# Callisto_Teknic_MSO_PBx4_v1p2.net
KiCad netlist of a schematic drawn in EAGLE
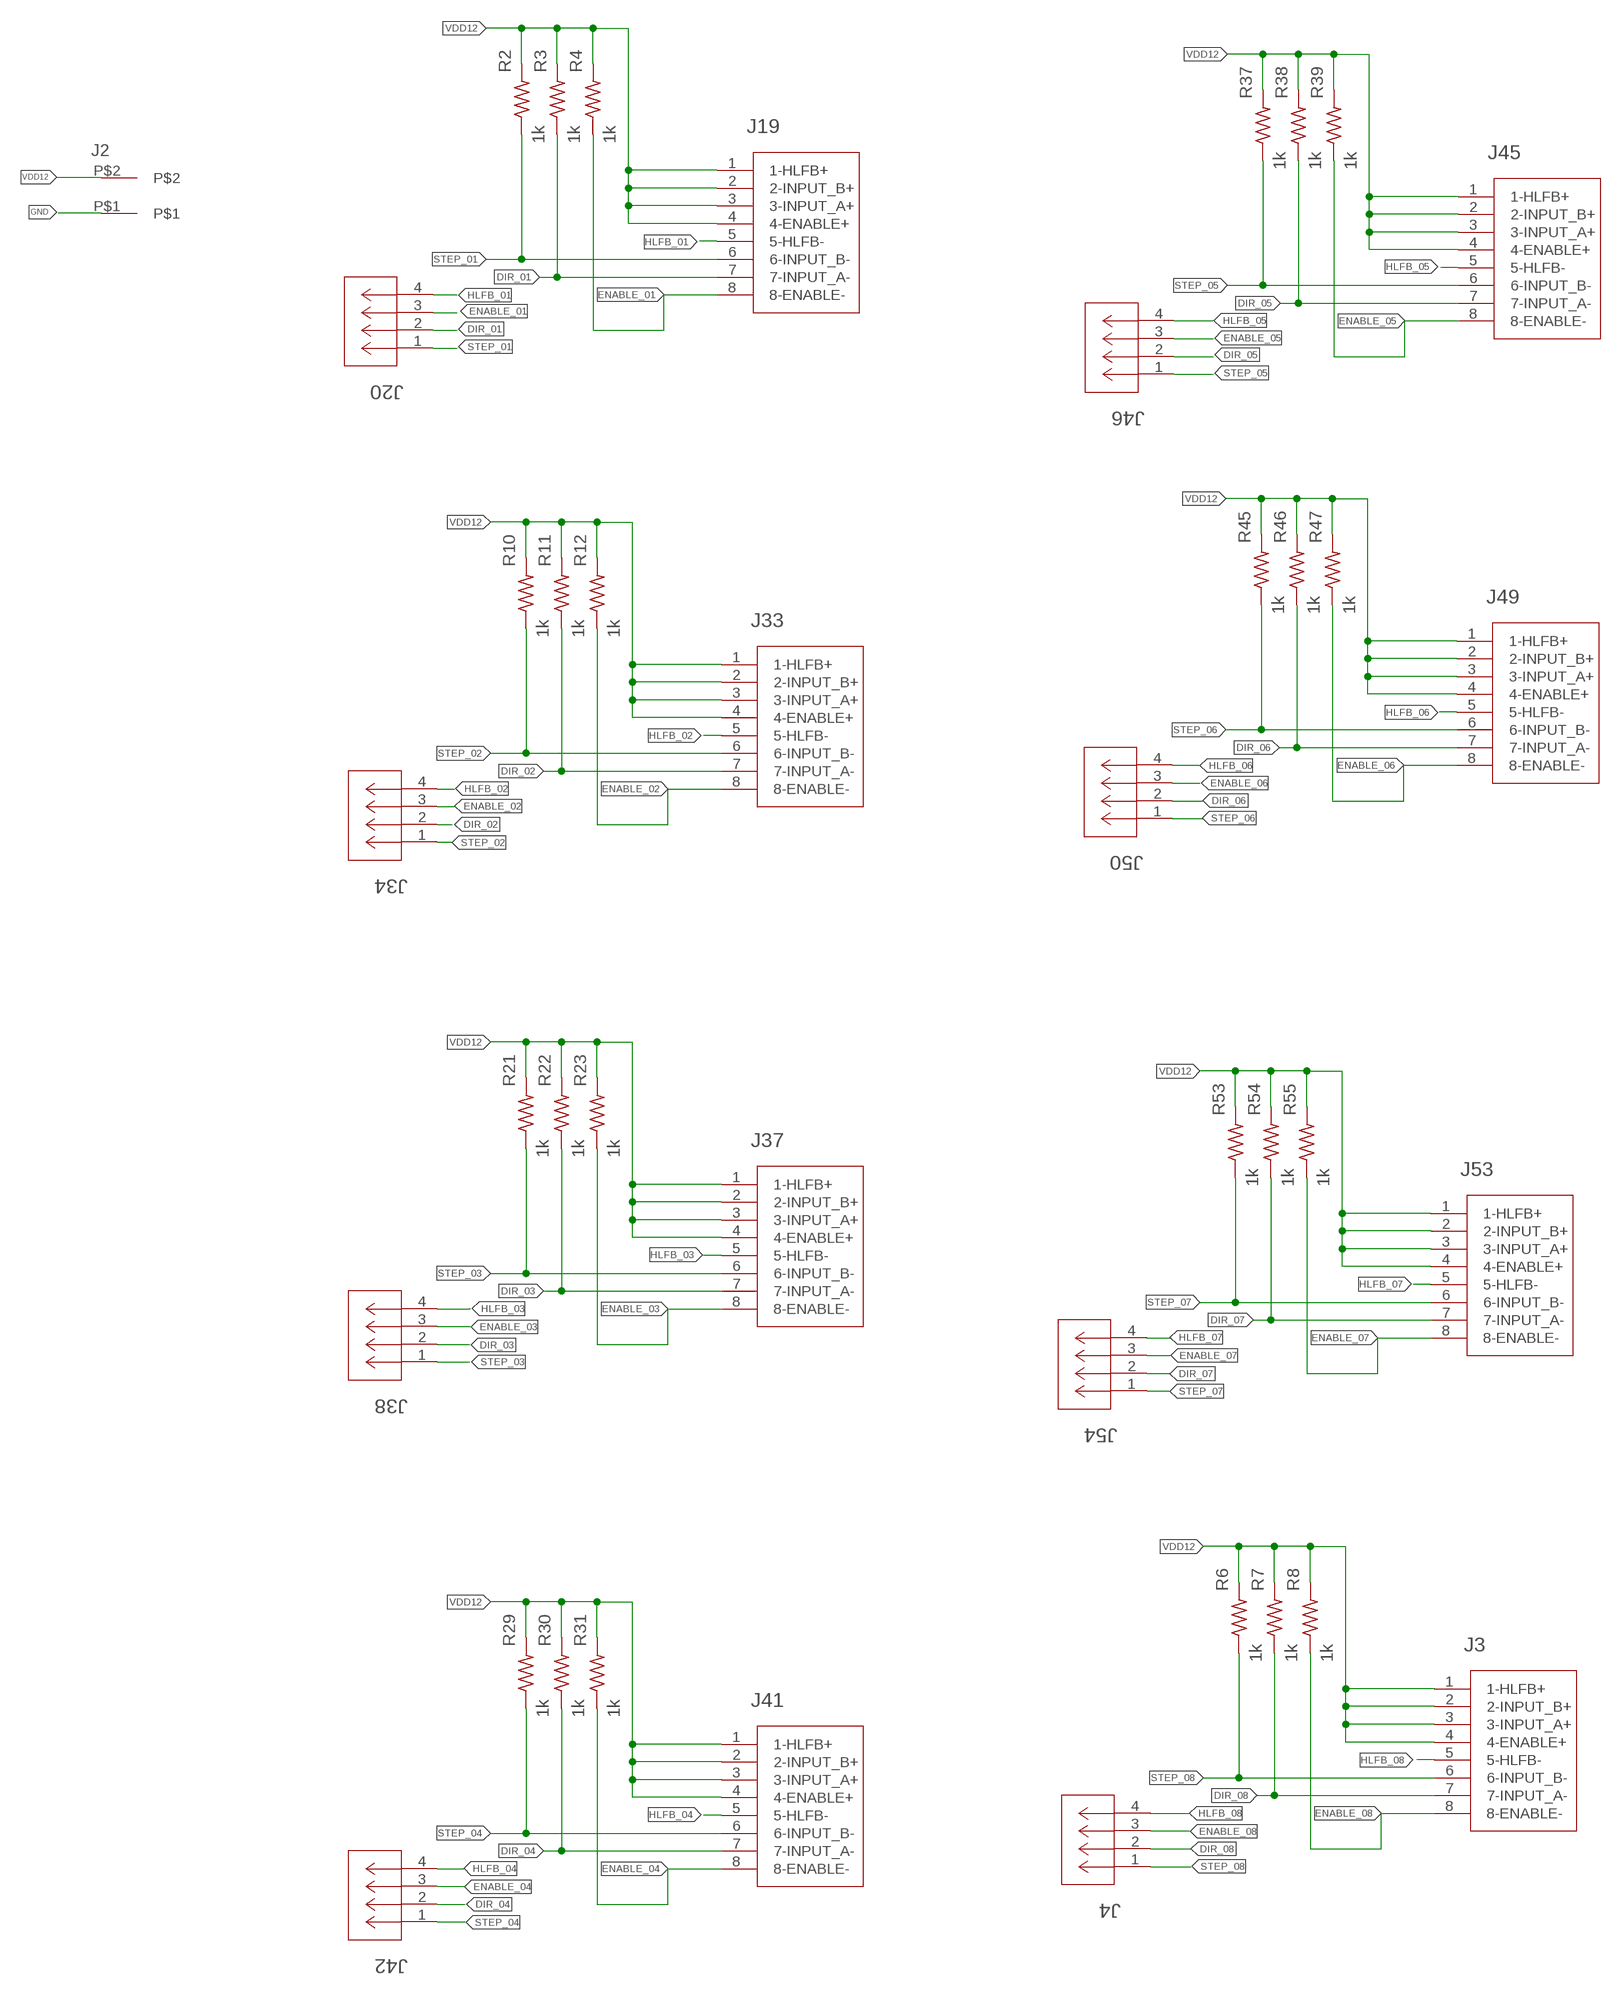
[diagram p0: schematic, sheet 1]

(export (version "E")
  (design (tool "Eeschema 10.0.6"))
  (components
    (comp (ref "J2")
      (value "2-pos")
      (footprint "eagle-import:2_3.81MM_PITCH")
      (fields (field (name "PARTNO") "691322310002"))
      (libsource (lib "eagle-import") (part "3.81MM_1_X_2_RT_ANGLE_PLUG_HEADER"))
    )
    (comp (ref "J3")
      (value "TEKNIC_8PIN_MOTOR")
      (footprint "eagle-import:CON_39281083")
      (fields
        (field (name "MANUFACTURER_PART_NUMBER") "39281083")
        (field (name "COPYRIGHT") "Copyright (C) 2022 Ultra Librarian. All rights reserved.")
      )
      (libsource (lib "eagle-import") (part "TEKNIC_8PIN_MOTOR"))
    )
    (comp (ref "J4")
      (value "CONN_530470410_PICOBLADE_X_4")
      (footprint "eagle-import:CON_530470410_MOL")
      (fields
        (field (name "MANUFACTURER_PART_NUMBER") "530470410")
        (field (name "COPYRIGHT") "Copyright (C) 2022 Ultra Librarian. All rights reserved.")
      )
      (libsource (lib "eagle-import") (part "CONN_530470410_PICOBLADE_X_4"))
    )
    (comp (ref "J19")
      (value "TEKNIC_8PIN_MOTOR")
      (footprint "eagle-import:CON_39281083")
      (fields
        (field (name "MANUFACTURER_PART_NUMBER") "39281083")
        (field (name "COPYRIGHT") "Copyright (C) 2022 Ultra Librarian. All rights reserved.")
      )
      (libsource (lib "eagle-import") (part "TEKNIC_8PIN_MOTOR"))
    )
    (comp (ref "J20")
      (value "CONN_530470410_PICOBLADE_X_4")
      (footprint "eagle-import:CON_530470410_MOL")
      (fields
        (field (name "MANUFACTURER_PART_NUMBER") "530470410")
        (field (name "COPYRIGHT") "Copyright (C) 2022 Ultra Librarian. All rights reserved.")
      )
      (libsource (lib "eagle-import") (part "CONN_530470410_PICOBLADE_X_4"))
    )
    (comp (ref "J33")
      (value "TEKNIC_8PIN_MOTOR")
      (footprint "eagle-import:CON_39281083")
      (fields
        (field (name "MANUFACTURER_PART_NUMBER") "39281083")
        (field (name "COPYRIGHT") "Copyright (C) 2022 Ultra Librarian. All rights reserved.")
      )
      (libsource (lib "eagle-import") (part "TEKNIC_8PIN_MOTOR"))
    )
    (comp (ref "J34")
      (value "CONN_530470410_PICOBLADE_X_4")
      (footprint "eagle-import:CON_530470410_MOL")
      (fields
        (field (name "MANUFACTURER_PART_NUMBER") "530470410")
        (field (name "COPYRIGHT") "Copyright (C) 2022 Ultra Librarian. All rights reserved.")
      )
      (libsource (lib "eagle-import") (part "CONN_530470410_PICOBLADE_X_4"))
    )
    (comp (ref "J37")
      (value "TEKNIC_8PIN_MOTOR")
      (footprint "eagle-import:CON_39281083")
      (fields
        (field (name "MANUFACTURER_PART_NUMBER") "39281083")
        (field (name "COPYRIGHT") "Copyright (C) 2022 Ultra Librarian. All rights reserved.")
      )
      (libsource (lib "eagle-import") (part "TEKNIC_8PIN_MOTOR"))
    )
    (comp (ref "J38")
      (value "CONN_530470410_PICOBLADE_X_4")
      (footprint "eagle-import:CON_530470410_MOL")
      (fields
        (field (name "MANUFACTURER_PART_NUMBER") "530470410")
        (field (name "COPYRIGHT") "Copyright (C) 2022 Ultra Librarian. All rights reserved.")
      )
      (libsource (lib "eagle-import") (part "CONN_530470410_PICOBLADE_X_4"))
    )
    (comp (ref "J41")
      (value "TEKNIC_8PIN_MOTOR")
      (footprint "eagle-import:CON_39281083")
      (fields
        (field (name "MANUFACTURER_PART_NUMBER") "39281083")
        (field (name "COPYRIGHT") "Copyright (C) 2022 Ultra Librarian. All rights reserved.")
      )
      (libsource (lib "eagle-import") (part "TEKNIC_8PIN_MOTOR"))
    )
    (comp (ref "J42")
      (value "CONN_530470410_PICOBLADE_X_4")
      (footprint "eagle-import:CON_530470410_MOL")
      (fields
        (field (name "MANUFACTURER_PART_NUMBER") "530470410")
        (field (name "COPYRIGHT") "Copyright (C) 2022 Ultra Librarian. All rights reserved.")
      )
      (libsource (lib "eagle-import") (part "CONN_530470410_PICOBLADE_X_4"))
    )
    (comp (ref "J45")
      (value "TEKNIC_8PIN_MOTOR")
      (footprint "eagle-import:CON_39281083")
      (fields
        (field (name "MANUFACTURER_PART_NUMBER") "39281083")
        (field (name "COPYRIGHT") "Copyright (C) 2022 Ultra Librarian. All rights reserved.")
      )
      (libsource (lib "eagle-import") (part "TEKNIC_8PIN_MOTOR"))
    )
    (comp (ref "J46")
      (value "CONN_530470410_PICOBLADE_X_4")
      (footprint "eagle-import:CON_530470410_MOL")
      (fields
        (field (name "MANUFACTURER_PART_NUMBER") "530470410")
        (field (name "COPYRIGHT") "Copyright (C) 2022 Ultra Librarian. All rights reserved.")
      )
      (libsource (lib "eagle-import") (part "CONN_530470410_PICOBLADE_X_4"))
    )
    (comp (ref "J49")
      (value "TEKNIC_8PIN_MOTOR")
      (footprint "eagle-import:CON_39281083")
      (fields
        (field (name "MANUFACTURER_PART_NUMBER") "39281083")
        (field (name "COPYRIGHT") "Copyright (C) 2022 Ultra Librarian. All rights reserved.")
      )
      (libsource (lib "eagle-import") (part "TEKNIC_8PIN_MOTOR"))
    )
    (comp (ref "J50")
      (value "CONN_530470410_PICOBLADE_X_4")
      (footprint "eagle-import:CON_530470410_MOL")
      (fields
        (field (name "MANUFACTURER_PART_NUMBER") "530470410")
        (field (name "COPYRIGHT") "Copyright (C) 2022 Ultra Librarian. All rights reserved.")
      )
      (libsource (lib "eagle-import") (part "CONN_530470410_PICOBLADE_X_4"))
    )
    (comp (ref "J53")
      (value "TEKNIC_8PIN_MOTOR")
      (footprint "eagle-import:CON_39281083")
      (fields
        (field (name "MANUFACTURER_PART_NUMBER") "39281083")
        (field (name "COPYRIGHT") "Copyright (C) 2022 Ultra Librarian. All rights reserved.")
      )
      (libsource (lib "eagle-import") (part "TEKNIC_8PIN_MOTOR"))
    )
    (comp (ref "J54")
      (value "CONN_530470410_PICOBLADE_X_4")
      (footprint "eagle-import:CON_530470410_MOL")
      (fields
        (field (name "MANUFACTURER_PART_NUMBER") "530470410")
        (field (name "COPYRIGHT") "Copyright (C) 2022 Ultra Librarian. All rights reserved.")
      )
      (libsource (lib "eagle-import") (part "CONN_530470410_PICOBLADE_X_4"))
    )
    (comp (ref "R2")
      (value "1k")
      (footprint "eagle-import:0805")
      (libsource (lib "eagle-import") (part "R_0805"))
    )
    (comp (ref "R3")
      (value "1k")
      (footprint "eagle-import:0805")
      (libsource (lib "eagle-import") (part "R_0805"))
    )
    (comp (ref "R4")
      (value "1k")
      (footprint "eagle-import:0805")
      (libsource (lib "eagle-import") (part "R_0805"))
    )
    (comp (ref "R6")
      (value "1k")
      (footprint "eagle-import:0805")
      (libsource (lib "eagle-import") (part "R_0805"))
    )
    (comp (ref "R7")
      (value "1k")
      (footprint "eagle-import:0805")
      (libsource (lib "eagle-import") (part "R_0805"))
    )
    (comp (ref "R8")
      (value "1k")
      (footprint "eagle-import:0805")
      (libsource (lib "eagle-import") (part "R_0805"))
    )
    (comp (ref "R10")
      (value "1k")
      (footprint "eagle-import:0805")
      (libsource (lib "eagle-import") (part "R_0805"))
    )
    (comp (ref "R11")
      (value "1k")
      (footprint "eagle-import:0805")
      (libsource (lib "eagle-import") (part "R_0805"))
    )
    (comp (ref "R12")
      (value "1k")
      (footprint "eagle-import:0805")
      (libsource (lib "eagle-import") (part "R_0805"))
    )
    (comp (ref "R21")
      (value "1k")
      (footprint "eagle-import:0805")
      (libsource (lib "eagle-import") (part "R_0805"))
    )
    (comp (ref "R22")
      (value "1k")
      (footprint "eagle-import:0805")
      (libsource (lib "eagle-import") (part "R_0805"))
    )
    (comp (ref "R23")
      (value "1k")
      (footprint "eagle-import:0805")
      (libsource (lib "eagle-import") (part "R_0805"))
    )
    (comp (ref "R29")
      (value "1k")
      (footprint "eagle-import:0805")
      (libsource (lib "eagle-import") (part "R_0805"))
    )
    (comp (ref "R30")
      (value "1k")
      (footprint "eagle-import:0805")
      (libsource (lib "eagle-import") (part "R_0805"))
    )
    (comp (ref "R31")
      (value "1k")
      (footprint "eagle-import:0805")
      (libsource (lib "eagle-import") (part "R_0805"))
    )
    (comp (ref "R37")
      (value "1k")
      (footprint "eagle-import:0805")
      (libsource (lib "eagle-import") (part "R_0805"))
    )
    (comp (ref "R38")
      (value "1k")
      (footprint "eagle-import:0805")
      (libsource (lib "eagle-import") (part "R_0805"))
    )
    (comp (ref "R39")
      (value "1k")
      (footprint "eagle-import:0805")
      (libsource (lib "eagle-import") (part "R_0805"))
    )
    (comp (ref "R45")
      (value "1k")
      (footprint "eagle-import:0805")
      (libsource (lib "eagle-import") (part "R_0805"))
    )
    (comp (ref "R46")
      (value "1k")
      (footprint "eagle-import:0805")
      (libsource (lib "eagle-import") (part "R_0805"))
    )
    (comp (ref "R47")
      (value "1k")
      (footprint "eagle-import:0805")
      (libsource (lib "eagle-import") (part "R_0805"))
    )
    (comp (ref "R53")
      (value "1k")
      (footprint "eagle-import:0805")
      (libsource (lib "eagle-import") (part "R_0805"))
    )
    (comp (ref "R54")
      (value "1k")
      (footprint "eagle-import:0805")
      (libsource (lib "eagle-import") (part "R_0805"))
    )
    (comp (ref "R55")
      (value "1k")
      (footprint "eagle-import:0805")
      (libsource (lib "eagle-import") (part "R_0805"))
    )
  )
  (nets
    (net (code "1") (name "DIR_01") (class "Default")
      (node (ref "J19") (pin "7") (pinfunction "7-INPUT_A-_7") (pintype "passive"))
      (node (ref "J20") (pin "2") (pinfunction "2_2") (pintype "passive"))
      (node (ref "R3") (pin "1") (pinfunction "1_1") (pintype "passive"))
    )
    (net (code "2") (name "DIR_02") (class "Default")
      (node (ref "J33") (pin "7") (pinfunction "7-INPUT_A-_7") (pintype "passive"))
      (node (ref "J34") (pin "2") (pinfunction "2_2") (pintype "passive"))
      (node (ref "R11") (pin "1") (pinfunction "1_1") (pintype "passive"))
    )
    (net (code "3") (name "DIR_03") (class "Default")
      (node (ref "J37") (pin "7") (pinfunction "7-INPUT_A-_7") (pintype "passive"))
      (node (ref "J38") (pin "2") (pinfunction "2_2") (pintype "passive"))
      (node (ref "R22") (pin "1") (pinfunction "1_1") (pintype "passive"))
    )
    (net (code "4") (name "DIR_04") (class "Default")
      (node (ref "J41") (pin "7") (pinfunction "7-INPUT_A-_7") (pintype "passive"))
      (node (ref "J42") (pin "2") (pinfunction "2_2") (pintype "passive"))
      (node (ref "R30") (pin "1") (pinfunction "1_1") (pintype "passive"))
    )
    (net (code "5") (name "DIR_05") (class "Default")
      (node (ref "J45") (pin "7") (pinfunction "7-INPUT_A-_7") (pintype "passive"))
      (node (ref "J46") (pin "2") (pinfunction "2_2") (pintype "passive"))
      (node (ref "R38") (pin "1") (pinfunction "1_1") (pintype "passive"))
    )
    (net (code "6") (name "DIR_06") (class "Default")
      (node (ref "J49") (pin "7") (pinfunction "7-INPUT_A-_7") (pintype "passive"))
      (node (ref "J50") (pin "2") (pinfunction "2_2") (pintype "passive"))
      (node (ref "R46") (pin "1") (pinfunction "1_1") (pintype "passive"))
    )
    (net (code "7") (name "DIR_07") (class "Default")
      (node (ref "J53") (pin "7") (pinfunction "7-INPUT_A-_7") (pintype "passive"))
      (node (ref "J54") (pin "2") (pinfunction "2_2") (pintype "passive"))
      (node (ref "R54") (pin "1") (pinfunction "1_1") (pintype "passive"))
    )
    (net (code "8") (name "DIR_08") (class "Default")
      (node (ref "J3") (pin "7") (pinfunction "7-INPUT_A-_7") (pintype "passive"))
      (node (ref "J4") (pin "2") (pinfunction "2_2") (pintype "passive"))
      (node (ref "R7") (pin "1") (pinfunction "1_1") (pintype "passive"))
    )
    (net (code "9") (name "ENABLE_01") (class "Default")
      (node (ref "J19") (pin "8") (pinfunction "8-ENABLE-_8") (pintype "passive"))
      (node (ref "J20") (pin "3") (pinfunction "3_3") (pintype "passive"))
      (node (ref "R4") (pin "1") (pinfunction "1_1") (pintype "passive"))
    )
    (net (code "10") (name "ENABLE_02") (class "Default")
      (node (ref "J33") (pin "8") (pinfunction "8-ENABLE-_8") (pintype "passive"))
      (node (ref "J34") (pin "3") (pinfunction "3_3") (pintype "passive"))
      (node (ref "R12") (pin "1") (pinfunction "1_1") (pintype "passive"))
    )
    (net (code "11") (name "ENABLE_03") (class "Default")
      (node (ref "J37") (pin "8") (pinfunction "8-ENABLE-_8") (pintype "passive"))
      (node (ref "J38") (pin "3") (pinfunction "3_3") (pintype "passive"))
      (node (ref "R23") (pin "1") (pinfunction "1_1") (pintype "passive"))
    )
    (net (code "12") (name "ENABLE_04") (class "Default")
      (node (ref "J41") (pin "8") (pinfunction "8-ENABLE-_8") (pintype "passive"))
      (node (ref "J42") (pin "3") (pinfunction "3_3") (pintype "passive"))
      (node (ref "R31") (pin "1") (pinfunction "1_1") (pintype "passive"))
    )
    (net (code "13") (name "ENABLE_05") (class "Default")
      (node (ref "J45") (pin "8") (pinfunction "8-ENABLE-_8") (pintype "passive"))
      (node (ref "J46") (pin "3") (pinfunction "3_3") (pintype "passive"))
      (node (ref "R39") (pin "1") (pinfunction "1_1") (pintype "passive"))
    )
    (net (code "14") (name "ENABLE_06") (class "Default")
      (node (ref "J49") (pin "8") (pinfunction "8-ENABLE-_8") (pintype "passive"))
      (node (ref "J50") (pin "3") (pinfunction "3_3") (pintype "passive"))
      (node (ref "R47") (pin "1") (pinfunction "1_1") (pintype "passive"))
    )
    (net (code "15") (name "ENABLE_07") (class "Default")
      (node (ref "J53") (pin "8") (pinfunction "8-ENABLE-_8") (pintype "passive"))
      (node (ref "J54") (pin "3") (pinfunction "3_3") (pintype "passive"))
      (node (ref "R55") (pin "1") (pinfunction "1_1") (pintype "passive"))
    )
    (net (code "16") (name "ENABLE_08") (class "Default")
      (node (ref "J3") (pin "8") (pinfunction "8-ENABLE-_8") (pintype "passive"))
      (node (ref "J4") (pin "3") (pinfunction "3_3") (pintype "passive"))
      (node (ref "R8") (pin "1") (pinfunction "1_1") (pintype "passive"))
    )
    (net (code "17") (name "GND") (class "Default")
      (node (ref "J2") (pin "P$1") (pinfunction "P$1_P$1") (pintype "bidirectional"))
    )
    (net (code "18") (name "HLFB_01") (class "Default")
      (node (ref "J19") (pin "5") (pinfunction "5-HLFB-_5") (pintype "passive"))
      (node (ref "J20") (pin "4") (pinfunction "4_4") (pintype "passive"))
    )
    (net (code "19") (name "HLFB_02") (class "Default")
      (node (ref "J33") (pin "5") (pinfunction "5-HLFB-_5") (pintype "passive"))
      (node (ref "J34") (pin "4") (pinfunction "4_4") (pintype "passive"))
    )
    (net (code "20") (name "HLFB_03") (class "Default")
      (node (ref "J37") (pin "5") (pinfunction "5-HLFB-_5") (pintype "passive"))
      (node (ref "J38") (pin "4") (pinfunction "4_4") (pintype "passive"))
    )
    (net (code "21") (name "HLFB_04") (class "Default")
      (node (ref "J41") (pin "5") (pinfunction "5-HLFB-_5") (pintype "passive"))
      (node (ref "J42") (pin "4") (pinfunction "4_4") (pintype "passive"))
    )
    (net (code "22") (name "HLFB_05") (class "Default")
      (node (ref "J45") (pin "5") (pinfunction "5-HLFB-_5") (pintype "passive"))
      (node (ref "J46") (pin "4") (pinfunction "4_4") (pintype "passive"))
    )
    (net (code "23") (name "HLFB_06") (class "Default")
      (node (ref "J49") (pin "5") (pinfunction "5-HLFB-_5") (pintype "passive"))
      (node (ref "J50") (pin "4") (pinfunction "4_4") (pintype "passive"))
    )
    (net (code "24") (name "HLFB_07") (class "Default")
      (node (ref "J53") (pin "5") (pinfunction "5-HLFB-_5") (pintype "passive"))
      (node (ref "J54") (pin "4") (pinfunction "4_4") (pintype "passive"))
    )
    (net (code "25") (name "HLFB_08") (class "Default")
      (node (ref "J3") (pin "5") (pinfunction "5-HLFB-_5") (pintype "passive"))
      (node (ref "J4") (pin "4") (pinfunction "4_4") (pintype "passive"))
    )
    (net (code "26") (name "STEP_01") (class "Default")
      (node (ref "J19") (pin "6") (pinfunction "6-INPUT_B-_6") (pintype "passive"))
      (node (ref "J20") (pin "1") (pinfunction "1_1") (pintype "passive"))
      (node (ref "R2") (pin "1") (pinfunction "1_1") (pintype "passive"))
    )
    (net (code "27") (name "STEP_02") (class "Default")
      (node (ref "J33") (pin "6") (pinfunction "6-INPUT_B-_6") (pintype "passive"))
      (node (ref "J34") (pin "1") (pinfunction "1_1") (pintype "passive"))
      (node (ref "R10") (pin "1") (pinfunction "1_1") (pintype "passive"))
    )
    (net (code "28") (name "STEP_03") (class "Default")
      (node (ref "J37") (pin "6") (pinfunction "6-INPUT_B-_6") (pintype "passive"))
      (node (ref "J38") (pin "1") (pinfunction "1_1") (pintype "passive"))
      (node (ref "R21") (pin "1") (pinfunction "1_1") (pintype "passive"))
    )
    (net (code "29") (name "STEP_04") (class "Default")
      (node (ref "J41") (pin "6") (pinfunction "6-INPUT_B-_6") (pintype "passive"))
      (node (ref "J42") (pin "1") (pinfunction "1_1") (pintype "passive"))
      (node (ref "R29") (pin "1") (pinfunction "1_1") (pintype "passive"))
    )
    (net (code "30") (name "STEP_05") (class "Default")
      (node (ref "J45") (pin "6") (pinfunction "6-INPUT_B-_6") (pintype "passive"))
      (node (ref "J46") (pin "1") (pinfunction "1_1") (pintype "passive"))
      (node (ref "R37") (pin "1") (pinfunction "1_1") (pintype "passive"))
    )
    (net (code "31") (name "STEP_06") (class "Default")
      (node (ref "J49") (pin "6") (pinfunction "6-INPUT_B-_6") (pintype "passive"))
      (node (ref "J50") (pin "1") (pinfunction "1_1") (pintype "passive"))
      (node (ref "R45") (pin "1") (pinfunction "1_1") (pintype "passive"))
    )
    (net (code "32") (name "STEP_07") (class "Default")
      (node (ref "J53") (pin "6") (pinfunction "6-INPUT_B-_6") (pintype "passive"))
      (node (ref "J54") (pin "1") (pinfunction "1_1") (pintype "passive"))
      (node (ref "R53") (pin "1") (pinfunction "1_1") (pintype "passive"))
    )
    (net (code "33") (name "STEP_08") (class "Default")
      (node (ref "J3") (pin "6") (pinfunction "6-INPUT_B-_6") (pintype "passive"))
      (node (ref "J4") (pin "1") (pinfunction "1_1") (pintype "passive"))
      (node (ref "R6") (pin "1") (pinfunction "1_1") (pintype "passive"))
    )
    (net (code "34") (name "VDD12") (class "Default")
      (node (ref "J19") (pin "1") (pinfunction "1-HLFB+_1") (pintype "passive"))
      (node (ref "J19") (pin "2") (pinfunction "2-INPUT_B+_2") (pintype "passive"))
      (node (ref "J19") (pin "3") (pinfunction "3-INPUT_A+_3") (pintype "passive"))
      (node (ref "J19") (pin "4") (pinfunction "4-ENABLE+_4") (pintype "passive"))
      (node (ref "J2") (pin "P$2") (pinfunction "P$2_P$2") (pintype "bidirectional"))
      (node (ref "J3") (pin "1") (pinfunction "1-HLFB+_1") (pintype "passive"))
      (node (ref "J3") (pin "2") (pinfunction "2-INPUT_B+_2") (pintype "passive"))
      (node (ref "J3") (pin "3") (pinfunction "3-INPUT_A+_3") (pintype "passive"))
      (node (ref "J3") (pin "4") (pinfunction "4-ENABLE+_4") (pintype "passive"))
      (node (ref "J33") (pin "1") (pinfunction "1-HLFB+_1") (pintype "passive"))
      (node (ref "J33") (pin "2") (pinfunction "2-INPUT_B+_2") (pintype "passive"))
      (node (ref "J33") (pin "3") (pinfunction "3-INPUT_A+_3") (pintype "passive"))
      (node (ref "J33") (pin "4") (pinfunction "4-ENABLE+_4") (pintype "passive"))
      (node (ref "J37") (pin "1") (pinfunction "1-HLFB+_1") (pintype "passive"))
      (node (ref "J37") (pin "2") (pinfunction "2-INPUT_B+_2") (pintype "passive"))
      (node (ref "J37") (pin "3") (pinfunction "3-INPUT_A+_3") (pintype "passive"))
      (node (ref "J37") (pin "4") (pinfunction "4-ENABLE+_4") (pintype "passive"))
      (node (ref "J41") (pin "1") (pinfunction "1-HLFB+_1") (pintype "passive"))
      (node (ref "J41") (pin "2") (pinfunction "2-INPUT_B+_2") (pintype "passive"))
      (node (ref "J41") (pin "3") (pinfunction "3-INPUT_A+_3") (pintype "passive"))
      (node (ref "J41") (pin "4") (pinfunction "4-ENABLE+_4") (pintype "passive"))
      (node (ref "J45") (pin "1") (pinfunction "1-HLFB+_1") (pintype "passive"))
      (node (ref "J45") (pin "2") (pinfunction "2-INPUT_B+_2") (pintype "passive"))
      (node (ref "J45") (pin "3") (pinfunction "3-INPUT_A+_3") (pintype "passive"))
      (node (ref "J45") (pin "4") (pinfunction "4-ENABLE+_4") (pintype "passive"))
      (node (ref "J49") (pin "1") (pinfunction "1-HLFB+_1") (pintype "passive"))
      (node (ref "J49") (pin "2") (pinfunction "2-INPUT_B+_2") (pintype "passive"))
      (node (ref "J49") (pin "3") (pinfunction "3-INPUT_A+_3") (pintype "passive"))
      (node (ref "J49") (pin "4") (pinfunction "4-ENABLE+_4") (pintype "passive"))
      (node (ref "J53") (pin "1") (pinfunction "1-HLFB+_1") (pintype "passive"))
      (node (ref "J53") (pin "2") (pinfunction "2-INPUT_B+_2") (pintype "passive"))
      (node (ref "J53") (pin "3") (pinfunction "3-INPUT_A+_3") (pintype "passive"))
      (node (ref "J53") (pin "4") (pinfunction "4-ENABLE+_4") (pintype "passive"))
      (node (ref "R10") (pin "2") (pinfunction "2_2") (pintype "passive"))
      (node (ref "R11") (pin "2") (pinfunction "2_2") (pintype "passive"))
      (node (ref "R12") (pin "2") (pinfunction "2_2") (pintype "passive"))
      (node (ref "R2") (pin "2") (pinfunction "2_2") (pintype "passive"))
      (node (ref "R21") (pin "2") (pinfunction "2_2") (pintype "passive"))
      (node (ref "R22") (pin "2") (pinfunction "2_2") (pintype "passive"))
      (node (ref "R23") (pin "2") (pinfunction "2_2") (pintype "passive"))
      (node (ref "R29") (pin "2") (pinfunction "2_2") (pintype "passive"))
      (node (ref "R3") (pin "2") (pinfunction "2_2") (pintype "passive"))
      (node (ref "R30") (pin "2") (pinfunction "2_2") (pintype "passive"))
      (node (ref "R31") (pin "2") (pinfunction "2_2") (pintype "passive"))
      (node (ref "R37") (pin "2") (pinfunction "2_2") (pintype "passive"))
      (node (ref "R38") (pin "2") (pinfunction "2_2") (pintype "passive"))
      (node (ref "R39") (pin "2") (pinfunction "2_2") (pintype "passive"))
      (node (ref "R4") (pin "2") (pinfunction "2_2") (pintype "passive"))
      (node (ref "R45") (pin "2") (pinfunction "2_2") (pintype "passive"))
      (node (ref "R46") (pin "2") (pinfunction "2_2") (pintype "passive"))
      (node (ref "R47") (pin "2") (pinfunction "2_2") (pintype "passive"))
      (node (ref "R53") (pin "2") (pinfunction "2_2") (pintype "passive"))
      (node (ref "R54") (pin "2") (pinfunction "2_2") (pintype "passive"))
      (node (ref "R55") (pin "2") (pinfunction "2_2") (pintype "passive"))
      (node (ref "R6") (pin "2") (pinfunction "2_2") (pintype "passive"))
      (node (ref "R7") (pin "2") (pinfunction "2_2") (pintype "passive"))
      (node (ref "R8") (pin "2") (pinfunction "2_2") (pintype "passive"))
    )
  )
)
